# Lvl_Shifters.net
KiCad netlist of a schematic drawn in Altium Designer
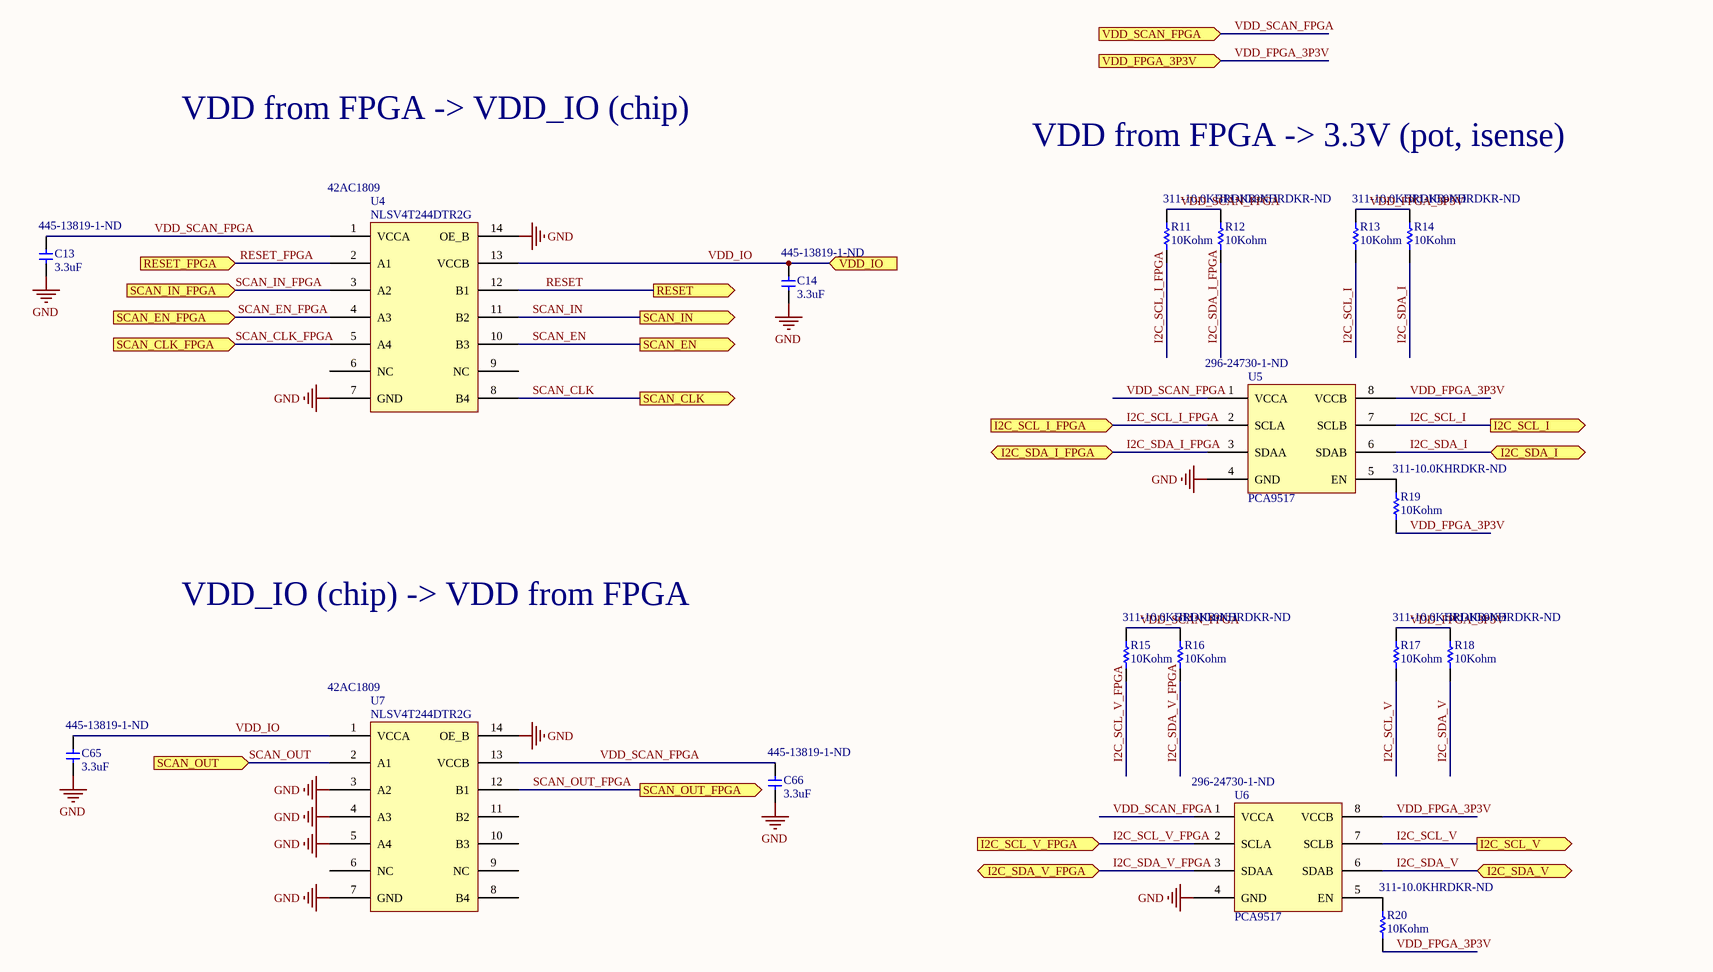
[diagram p0: Lvl_Shifters.SchDoc]

(export (version "E")
  (design (tool "Eeschema 10.0.6"))
  (components
    (comp (ref "C13")
      (value "3.3uF")
      (footprint "CAP_0402")
      (description "CAP CER 3.3uF 10% 10V X5R 0402")
      (fields (field (name "MANUFACTURER") "TDK") (field (name "SUPPLIER PART NUMBER 1") "445-13819-1-ND"))
      (libsource (lib "fader2_parts") (part "cap 3p3uF"))
    )
    (comp (ref "C14")
      (value "3.3uF")
      (footprint "CAP_0402")
      (description "CAP CER 3.3uF 10% 10V X5R 0402")
      (fields (field (name "MANUFACTURER") "TDK") (field (name "SUPPLIER PART NUMBER 1") "445-13819-1-ND"))
      (libsource (lib "fader2_parts") (part "cap 3p3uF"))
    )
    (comp (ref "C65")
      (value "3.3uF")
      (footprint "CAP_0402")
      (description "CAP CER 3.3uF 10% 10V X5R 0402")
      (fields (field (name "MANUFACTURER") "TDK") (field (name "SUPPLIER PART NUMBER 1") "445-13819-1-ND"))
      (libsource (lib "fader2_parts") (part "cap 3p3uF"))
    )
    (comp (ref "C66")
      (value "3.3uF")
      (footprint "CAP_0402")
      (description "CAP CER 3.3uF 10% 10V X5R 0402")
      (fields (field (name "MANUFACTURER") "TDK") (field (name "SUPPLIER PART NUMBER 1") "445-13819-1-ND"))
      (libsource (lib "fader2_parts") (part "cap 3p3uF"))
    )
    (comp (ref "R11")
      (value "10Kohm")
      (footprint "RES_0603")
      (description "RES SMD 10k OHM 1% 1/10W 0603")
      (fields (field (name "SUPPLIER PART NUMBER 1") "311-10.0KHRDKR-ND"))
      (libsource (lib "fader2_parts") (part "res 10 kOhm_1"))
    )
    (comp (ref "R12")
      (value "10Kohm")
      (footprint "RES_0603")
      (description "RES SMD 10k OHM 1% 1/10W 0603")
      (fields (field (name "SUPPLIER PART NUMBER 1") "311-10.0KHRDKR-ND"))
      (libsource (lib "fader2_parts") (part "res 10 kOhm_1"))
    )
    (comp (ref "R13")
      (value "10Kohm")
      (footprint "RES_0603")
      (description "RES SMD 10k OHM 1% 1/10W 0603")
      (fields (field (name "SUPPLIER PART NUMBER 1") "311-10.0KHRDKR-ND"))
      (libsource (lib "fader2_parts") (part "res 10 kOhm_1"))
    )
    (comp (ref "R14")
      (value "10Kohm")
      (footprint "RES_0603")
      (description "RES SMD 10k OHM 1% 1/10W 0603")
      (fields (field (name "SUPPLIER PART NUMBER 1") "311-10.0KHRDKR-ND"))
      (libsource (lib "fader2_parts") (part "res 10 kOhm_1"))
    )
    (comp (ref "R15")
      (value "10Kohm")
      (footprint "RES_0603")
      (description "RES SMD 10k OHM 1% 1/10W 0603")
      (fields (field (name "SUPPLIER PART NUMBER 1") "311-10.0KHRDKR-ND"))
      (libsource (lib "fader2_parts") (part "res 10 kOhm_1"))
    )
    (comp (ref "R16")
      (value "10Kohm")
      (footprint "RES_0603")
      (description "RES SMD 10k OHM 1% 1/10W 0603")
      (fields (field (name "SUPPLIER PART NUMBER 1") "311-10.0KHRDKR-ND"))
      (libsource (lib "fader2_parts") (part "res 10 kOhm_1"))
    )
    (comp (ref "R17")
      (value "10Kohm")
      (footprint "RES_0603")
      (description "RES SMD 10k OHM 1% 1/10W 0603")
      (fields (field (name "SUPPLIER PART NUMBER 1") "311-10.0KHRDKR-ND"))
      (libsource (lib "fader2_parts") (part "res 10 kOhm_1"))
    )
    (comp (ref "R18")
      (value "10Kohm")
      (footprint "RES_0603")
      (description "RES SMD 10k OHM 1% 1/10W 0603")
      (fields (field (name "SUPPLIER PART NUMBER 1") "311-10.0KHRDKR-ND"))
      (libsource (lib "fader2_parts") (part "res 10 kOhm_1"))
    )
    (comp (ref "R19")
      (value "10Kohm")
      (footprint "RES_0603")
      (description "RES SMD 10k OHM 1% 1/10W 0603")
      (fields (field (name "SUPPLIER PART NUMBER 1") "311-10.0KHRDKR-ND"))
      (libsource (lib "fader2_parts") (part "res 10 kOhm_1"))
    )
    (comp (ref "R20")
      (value "10Kohm")
      (footprint "RES_0603")
      (description "RES SMD 10k OHM 1% 1/10W 0603")
      (fields (field (name "SUPPLIER PART NUMBER 1") "311-10.0KHRDKR-ND"))
      (libsource (lib "fader2_parts") (part "res 10 kOhm_1"))
    )
    (comp (ref "U4")
      (value "NLSV4T244DTR2G")
      (footprint "948G-01")
      (description "Voltage Level Translator Unidirectional 1 Circuit 4 Channel 14-TSSOP")
      (fields
        (field (name "MANUFACTURER") "ON Semiconductor")
        (field (name "SUPPLIER PART NUMBER 1") "42AC1809")
      )
      (libsource (lib "fader2_parts") (part "NLSV4T244"))
    )
    (comp (ref "U5")
      (value "PCA9517")
      (footprint "PCA9517")
      (description "I2C Repeater, Buffer, ReDriver 2 Channel 400kHz 8-VSSOP")
      (fields (field (name "MANUFACTURER") "TI") (field (name "SUPPLIER PART NUMBER 1") "296-24730-1-ND"))
      (libsource (lib "fader2_parts") (part "PCA9517"))
    )
    (comp (ref "U6")
      (value "PCA9517")
      (footprint "PCA9517")
      (description "I2C Repeater, Buffer, ReDriver 2 Channel 400kHz 8-VSSOP")
      (fields (field (name "MANUFACTURER") "TI") (field (name "SUPPLIER PART NUMBER 1") "296-24730-1-ND"))
      (libsource (lib "fader2_parts") (part "PCA9517"))
    )
    (comp (ref "U7")
      (value "NLSV4T244DTR2G")
      (footprint "948G-01")
      (description "Voltage Level Translator Unidirectional 1 Circuit 4 Channel 14-TSSOP")
      (fields
        (field (name "MANUFACTURER") "ON Semiconductor")
        (field (name "SUPPLIER PART NUMBER 1") "42AC1809")
      )
      (libsource (lib "fader2_parts") (part "NLSV4T244"))
    )
  )
  (nets
    (net (code "1") (name "/I2C_SCL_I") (class "Default")
      (node (ref "R13") (pin "2") (pinfunction "BOT_2") (pintype "passive"))
      (node (ref "U5") (pin "7") (pinfunction "SCLB_7") (pintype "passive"))
    )
    (net (code "2") (name "/I2C_SCL_I_FPGA") (class "Default")
      (node (ref "R11") (pin "2") (pinfunction "BOT_2") (pintype "passive"))
      (node (ref "U5") (pin "2") (pinfunction "SCLA_2") (pintype "passive"))
    )
    (net (code "3") (name "/I2C_SCL_V") (class "Default")
      (node (ref "R17") (pin "2") (pinfunction "BOT_2") (pintype "passive"))
      (node (ref "U6") (pin "7") (pinfunction "SCLB_7") (pintype "passive"))
    )
    (net (code "4") (name "/I2C_SCL_V_FPGA") (class "Default")
      (node (ref "R15") (pin "2") (pinfunction "BOT_2") (pintype "passive"))
      (node (ref "U6") (pin "2") (pinfunction "SCLA_2") (pintype "passive"))
    )
    (net (code "5") (name "/I2C_SDA_I") (class "Default")
      (node (ref "R14") (pin "2") (pinfunction "BOT_2") (pintype "passive"))
      (node (ref "U5") (pin "6") (pinfunction "SDAB_6") (pintype "passive"))
    )
    (net (code "6") (name "/I2C_SDA_I_FPGA") (class "Default")
      (node (ref "R12") (pin "2") (pinfunction "BOT_2") (pintype "passive"))
      (node (ref "U5") (pin "3") (pinfunction "SDAA_3") (pintype "passive"))
    )
    (net (code "7") (name "/I2C_SDA_V") (class "Default")
      (node (ref "R18") (pin "2") (pinfunction "BOT_2") (pintype "passive"))
      (node (ref "U6") (pin "6") (pinfunction "SDAB_6") (pintype "passive"))
    )
    (net (code "8") (name "/I2C_SDA_V_FPGA") (class "Default")
      (node (ref "R16") (pin "2") (pinfunction "BOT_2") (pintype "passive"))
      (node (ref "U6") (pin "3") (pinfunction "SDAA_3") (pintype "passive"))
    )
    (net (code "9") (name "/RESET") (class "Default")
      (node (ref "U4") (pin "12") (pinfunction "B1_12") (pintype "passive"))
    )
    (net (code "10") (name "/RESET_FPGA") (class "Default")
      (node (ref "U4") (pin "2") (pinfunction "A1_2") (pintype "passive"))
    )
    (net (code "11") (name "/SCAN_CLK") (class "Default")
      (node (ref "U4") (pin "8") (pinfunction "B4_8") (pintype "passive"))
    )
    (net (code "12") (name "/SCAN_CLK_FPGA") (class "Default")
      (node (ref "U4") (pin "5") (pinfunction "A4_5") (pintype "passive"))
    )
    (net (code "13") (name "/SCAN_EN") (class "Default")
      (node (ref "U4") (pin "10") (pinfunction "B3_10") (pintype "passive"))
    )
    (net (code "14") (name "/SCAN_EN_FPGA") (class "Default")
      (node (ref "U4") (pin "4") (pinfunction "A3_4") (pintype "passive"))
    )
    (net (code "15") (name "/SCAN_IN") (class "Default")
      (node (ref "U4") (pin "11") (pinfunction "B2_11") (pintype "passive"))
    )
    (net (code "16") (name "/SCAN_IN_FPGA") (class "Default")
      (node (ref "U4") (pin "3") (pinfunction "A2_3") (pintype "passive"))
    )
    (net (code "17") (name "/SCAN_OUT") (class "Default")
      (node (ref "U7") (pin "2") (pinfunction "A1_2") (pintype "passive"))
    )
    (net (code "18") (name "/SCAN_OUT_FPGA") (class "Default")
      (node (ref "U7") (pin "12") (pinfunction "B1_12") (pintype "passive"))
    )
    (net (code "19") (name "/VDD_FPGA_3P3V") (class "Default")
      (node (ref "R13") (pin "1") (pinfunction "TOP_1") (pintype "passive"))
      (node (ref "R14") (pin "1") (pinfunction "TOP_1") (pintype "passive"))
      (node (ref "R17") (pin "1") (pinfunction "TOP_1") (pintype "passive"))
      (node (ref "R18") (pin "1") (pinfunction "TOP_1") (pintype "passive"))
      (node (ref "R19") (pin "2") (pinfunction "BOT_2") (pintype "passive"))
      (node (ref "R20") (pin "2") (pinfunction "BOT_2") (pintype "passive"))
      (node (ref "U5") (pin "8") (pinfunction "VCCB_8") (pintype "passive"))
      (node (ref "U6") (pin "8") (pinfunction "VCCB_8") (pintype "passive"))
    )
    (net (code "20") (name "/VDD_IO") (class "Default")
      (node (ref "C14") (pin "1") (pinfunction "1_1") (pintype "passive"))
      (node (ref "C65") (pin "1") (pinfunction "1_1") (pintype "passive"))
      (node (ref "U4") (pin "13") (pinfunction "VCCB_13") (pintype "passive"))
      (node (ref "U7") (pin "1") (pinfunction "VCCA_1") (pintype "passive"))
    )
    (net (code "21") (name "/VDD_SCAN_FPGA") (class "Default")
      (node (ref "C13") (pin "1") (pinfunction "1_1") (pintype "passive"))
      (node (ref "C66") (pin "1") (pinfunction "1_1") (pintype "passive"))
      (node (ref "R11") (pin "1") (pinfunction "TOP_1") (pintype "passive"))
      (node (ref "R12") (pin "1") (pinfunction "TOP_1") (pintype "passive"))
      (node (ref "R15") (pin "1") (pinfunction "TOP_1") (pintype "passive"))
      (node (ref "R16") (pin "1") (pinfunction "TOP_1") (pintype "passive"))
      (node (ref "U4") (pin "1") (pinfunction "VCCA_1") (pintype "passive"))
      (node (ref "U5") (pin "1") (pinfunction "VCCA_1") (pintype "passive"))
      (node (ref "U6") (pin "1") (pinfunction "VCCA_1") (pintype "passive"))
      (node (ref "U7") (pin "13") (pinfunction "VCCB_13") (pintype "passive"))
    )
    (net (code "22") (name "GND") (class "Default")
      (node (ref "C13") (pin "2") (pinfunction "2_2") (pintype "passive"))
      (node (ref "C14") (pin "2") (pinfunction "2_2") (pintype "passive"))
      (node (ref "C65") (pin "2") (pinfunction "2_2") (pintype "passive"))
      (node (ref "C66") (pin "2") (pinfunction "2_2") (pintype "passive"))
      (node (ref "U4") (pin "14") (pinfunction "OE_B_14") (pintype "passive"))
      (node (ref "U4") (pin "7") (pinfunction "GND_7") (pintype "passive"))
      (node (ref "U5") (pin "4") (pinfunction "GND_4") (pintype "passive"))
      (node (ref "U6") (pin "4") (pinfunction "GND_4") (pintype "passive"))
      (node (ref "U7") (pin "14") (pinfunction "OE_B_14") (pintype "passive"))
      (node (ref "U7") (pin "3") (pinfunction "A2_3") (pintype "passive"))
      (node (ref "U7") (pin "4") (pinfunction "A3_4") (pintype "passive"))
      (node (ref "U7") (pin "5") (pinfunction "A4_5") (pintype "passive"))
      (node (ref "U7") (pin "7") (pinfunction "GND_7") (pintype "passive"))
    )
    (net (code "23") (name "Net-(R19-TOP)") (class "Default")
      (node (ref "R19") (pin "1") (pinfunction "TOP_1") (pintype "passive"))
      (node (ref "U5") (pin "5") (pinfunction "EN_5") (pintype "passive"))
    )
    (net (code "24") (name "Net-(R20-TOP)") (class "Default")
      (node (ref "R20") (pin "1") (pinfunction "TOP_1") (pintype "passive"))
      (node (ref "U6") (pin "5") (pinfunction "EN_5") (pintype "passive"))
    )
    (net (code "25") (name "unconnected-(U4-NC-Pad6)") (class "Default")
      (node (ref "U4") (pin "6") (pinfunction "NC_6") (pintype "passive"))
    )
    (net (code "26") (name "unconnected-(U4-NC-Pad9)") (class "Default")
      (node (ref "U4") (pin "9") (pinfunction "NC_9") (pintype "passive"))
    )
    (net (code "27") (name "unconnected-(U7-B2-Pad11)") (class "Default")
      (node (ref "U7") (pin "11") (pinfunction "B2_11") (pintype "passive"))
    )
    (net (code "28") (name "unconnected-(U7-B3-Pad10)") (class "Default")
      (node (ref "U7") (pin "10") (pinfunction "B3_10") (pintype "passive"))
    )
    (net (code "29") (name "unconnected-(U7-B4-Pad8)") (class "Default")
      (node (ref "U7") (pin "8") (pinfunction "B4_8") (pintype "passive"))
    )
    (net (code "30") (name "unconnected-(U7-NC-Pad6)") (class "Default")
      (node (ref "U7") (pin "6") (pinfunction "NC_6") (pintype "passive"))
    )
    (net (code "31") (name "unconnected-(U7-NC-Pad9)") (class "Default")
      (node (ref "U7") (pin "9") (pinfunction "NC_9") (pintype "passive"))
    )
  )
)
